# Schematic.net
KiCad netlist of a schematic drawn in EAGLE
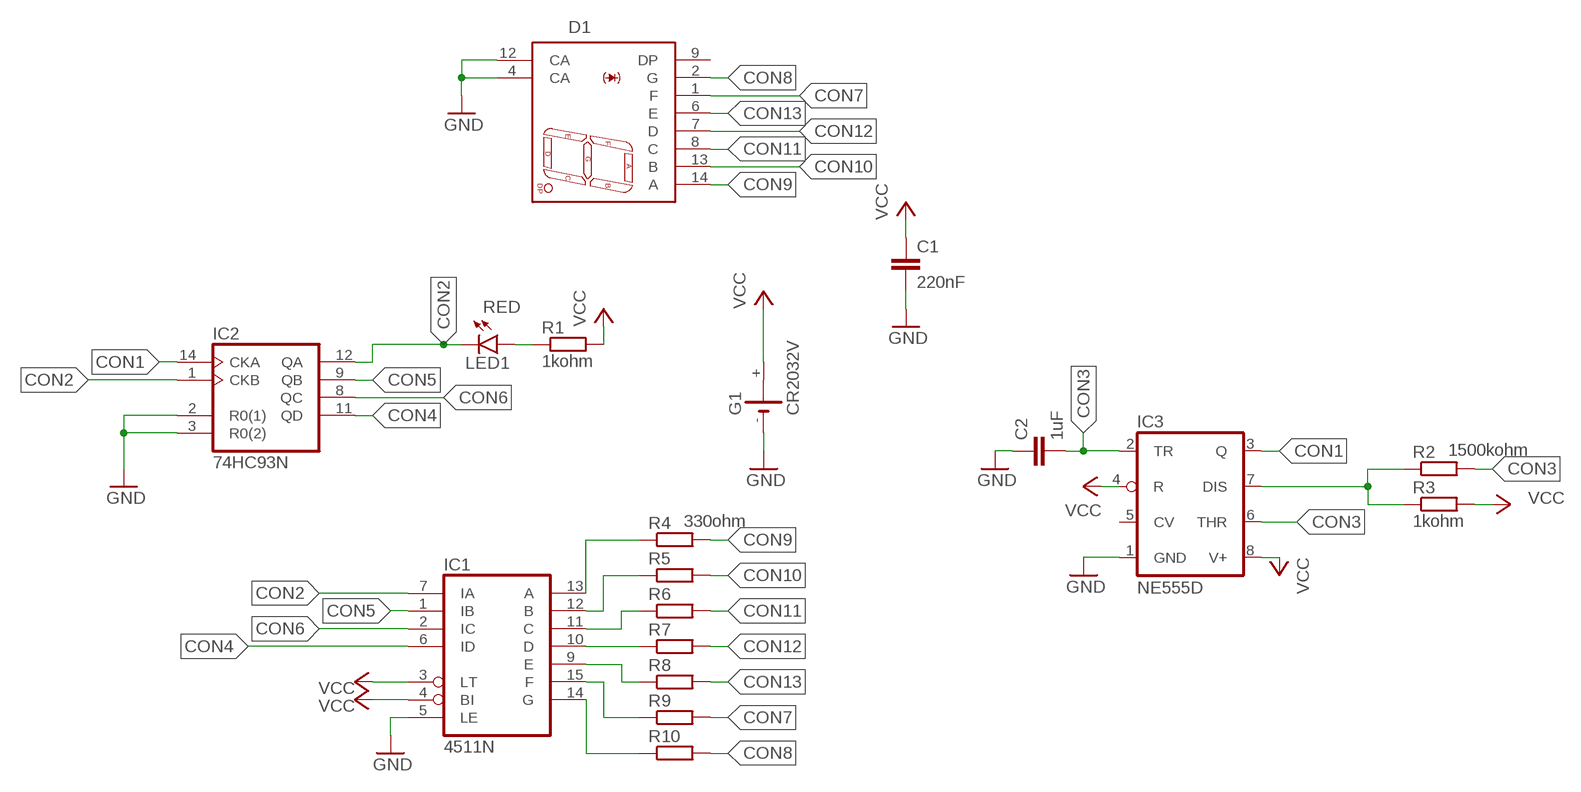
[diagram p0: schematic, sheet 1]

(export (version "E")
  (design (tool "Eeschema 10.0.6"))
  (components
    (comp (ref "C1")
      (value "220nF")
      (footprint "eagle-import:C025-025X050")
      (libsource (lib "eagle-import") (part "C-EU025-025X050"))
    )
    (comp (ref "C2")
      (value "1uF")
      (footprint "eagle-import:C025-025X050")
      (libsource (lib "eagle-import") (part "C-EU025-025X050"))
    )
    (comp (ref "D1")
      (value "SA03")
      (footprint "eagle-import:S_03")
      (libsource (lib "eagle-import") (part "SA03"))
    )
    (comp (ref "G1")
      (value "CR2032V")
      (footprint "eagle-import:CR2032V")
      (libsource (lib "eagle-import") (part "CR2032V"))
    )
    (comp (ref "IC1")
      (value "4511N")
      (footprint "eagle-import:DIL16")
      (libsource (lib "eagle-import") (part "4511N"))
    )
    (comp (ref "IC2")
      (value "74HC93N")
      (footprint "eagle-import:DIL14")
      (libsource (lib "eagle-import") (part "7493NHC"))
    )
    (comp (ref "IC3")
      (value "NE555D")
      (footprint "eagle-import:SO08")
      (libsource (lib "eagle-import") (part "555DNE"))
    )
    (comp (ref "LED1")
      (value "RED")
      (footprint "eagle-import:LED3MM")
      (libsource (lib "eagle-import") (part "LED3MM"))
    )
    (comp (ref "R1")
      (value "1kohm")
      (footprint "eagle-import:0204_7")
      (libsource (lib "eagle-import") (part "R-EU_0204/7"))
    )
    (comp (ref "R2")
      (value "1500kohm")
      (footprint "eagle-import:0204_7")
      (libsource (lib "eagle-import") (part "R-EU_0204/7"))
    )
    (comp (ref "R3")
      (value "1kohm")
      (footprint "eagle-import:0204_7")
      (libsource (lib "eagle-import") (part "R-EU_0204/7"))
    )
    (comp (ref "R4")
      (value "330ohm")
      (footprint "eagle-import:0204_7")
      (libsource (lib "eagle-import") (part "R-EU_0204/7"))
    )
    (comp (ref "R5")
      (value "R-EU_0204/7")
      (footprint "eagle-import:0204_7")
      (libsource (lib "eagle-import") (part "R-EU_0204/7"))
    )
    (comp (ref "R6")
      (value "R-EU_0204/7")
      (footprint "eagle-import:0204_7")
      (libsource (lib "eagle-import") (part "R-EU_0204/7"))
    )
    (comp (ref "R7")
      (value "R-EU_0204/7")
      (footprint "eagle-import:0204_7")
      (libsource (lib "eagle-import") (part "R-EU_0204/7"))
    )
    (comp (ref "R8")
      (value "R-EU_0204/7")
      (footprint "eagle-import:0204_7")
      (libsource (lib "eagle-import") (part "R-EU_0204/7"))
    )
    (comp (ref "R9")
      (value "R-EU_0204/7")
      (footprint "eagle-import:0204_7")
      (libsource (lib "eagle-import") (part "R-EU_0204/7"))
    )
    (comp (ref "R10")
      (value "R-EU_0204/7")
      (footprint "eagle-import:0204_7")
      (libsource (lib "eagle-import") (part "R-EU_0204/7"))
    )
  )
  (nets
    (net (code "1") (name "CON1") (class "Default")
      (node (ref "IC2") (pin "14") (pinfunction "CKA_14") (pintype "input"))
      (node (ref "IC3") (pin "3") (pinfunction "Q_3") (pintype "output"))
    )
    (net (code "2") (name "CON2") (class "Default")
      (node (ref "IC1") (pin "7") (pinfunction "IA_7") (pintype "input"))
      (node (ref "IC2") (pin "1") (pinfunction "CKB_1") (pintype "input"))
      (node (ref "IC2") (pin "12") (pinfunction "QA_12") (pintype "output"))
      (node (ref "LED1") (pin "K") (pinfunction "C_K") (pintype "passive"))
    )
    (net (code "3") (name "CON3") (class "Default")
      (node (ref "C2") (pin "2") (pinfunction "2_2") (pintype "passive"))
      (node (ref "IC3") (pin "2") (pinfunction "TR_2") (pintype "input"))
      (node (ref "IC3") (pin "6") (pinfunction "THR_6") (pintype "input"))
      (node (ref "R2") (pin "2") (pinfunction "2_2") (pintype "passive"))
    )
    (net (code "4") (name "CON4") (class "Default")
      (node (ref "IC1") (pin "6") (pinfunction "ID_6") (pintype "input"))
      (node (ref "IC2") (pin "11") (pinfunction "QD_11") (pintype "output"))
    )
    (net (code "5") (name "CON5") (class "Default")
      (node (ref "IC1") (pin "1") (pinfunction "IB_1") (pintype "input"))
      (node (ref "IC2") (pin "9") (pinfunction "QB_9") (pintype "output"))
    )
    (net (code "6") (name "CON6") (class "Default")
      (node (ref "IC1") (pin "2") (pinfunction "IC_2") (pintype "input"))
      (node (ref "IC2") (pin "8") (pinfunction "QC_8") (pintype "output"))
    )
    (net (code "7") (name "CON7") (class "Default")
      (node (ref "D1") (pin "1") (pinfunction "F_1") (pintype "passive"))
      (node (ref "R9") (pin "2") (pinfunction "2_2") (pintype "passive"))
    )
    (net (code "8") (name "CON8") (class "Default")
      (node (ref "D1") (pin "2") (pinfunction "G_2") (pintype "passive"))
      (node (ref "R10") (pin "2") (pinfunction "2_2") (pintype "passive"))
    )
    (net (code "9") (name "CON9") (class "Default")
      (node (ref "D1") (pin "14") (pinfunction "A_14") (pintype "passive"))
      (node (ref "R4") (pin "2") (pinfunction "2_2") (pintype "passive"))
    )
    (net (code "10") (name "CON10") (class "Default")
      (node (ref "D1") (pin "13") (pinfunction "B_13") (pintype "passive"))
      (node (ref "R5") (pin "2") (pinfunction "2_2") (pintype "passive"))
    )
    (net (code "11") (name "CON11") (class "Default")
      (node (ref "D1") (pin "8") (pinfunction "C_8") (pintype "passive"))
      (node (ref "R6") (pin "2") (pinfunction "2_2") (pintype "passive"))
    )
    (net (code "12") (name "CON12") (class "Default")
      (node (ref "D1") (pin "7") (pinfunction "D_7") (pintype "passive"))
      (node (ref "R7") (pin "2") (pinfunction "2_2") (pintype "passive"))
    )
    (net (code "13") (name "CON13") (class "Default")
      (node (ref "D1") (pin "6") (pinfunction "E_6") (pintype "passive"))
      (node (ref "R8") (pin "2") (pinfunction "2_2") (pintype "passive"))
    )
    (net (code "14") (name "GND") (class "Default")
      (node (ref "C1") (pin "2") (pinfunction "2_2") (pintype "passive"))
      (node (ref "C2") (pin "1") (pinfunction "1_1") (pintype "passive"))
      (node (ref "D1") (pin "12") (pinfunction "CA_12") (pintype "passive"))
      (node (ref "D1") (pin "4") (pinfunction "CA_4") (pintype "passive"))
      (node (ref "G1") (pin "-") (pinfunction "-_-") (pintype "passive"))
      (node (ref "IC1") (pin "5") (pinfunction "LE_5") (pintype "input"))
      (node (ref "IC2") (pin "2") (pinfunction "R0(1)_2") (pintype "input"))
      (node (ref "IC2") (pin "3") (pinfunction "R0(2)_3") (pintype "input"))
      (node (ref "IC3") (pin "1") (pinfunction "GND_1") (pintype "power_in"))
    )
    (net (code "15") (name "Net-(IC1A-A)") (class "Default")
      (node (ref "IC1") (pin "13") (pinfunction "A_13") (pintype "output"))
      (node (ref "R4") (pin "1") (pinfunction "1_1") (pintype "passive"))
    )
    (net (code "16") (name "Net-(IC1A-B)") (class "Default")
      (node (ref "IC1") (pin "12") (pinfunction "B_12") (pintype "output"))
      (node (ref "R5") (pin "1") (pinfunction "1_1") (pintype "passive"))
    )
    (net (code "17") (name "Net-(IC1A-C)") (class "Default")
      (node (ref "IC1") (pin "11") (pinfunction "C_11") (pintype "output"))
      (node (ref "R6") (pin "1") (pinfunction "1_1") (pintype "passive"))
    )
    (net (code "18") (name "Net-(IC1A-D)") (class "Default")
      (node (ref "IC1") (pin "10") (pinfunction "D_10") (pintype "output"))
      (node (ref "R7") (pin "1") (pinfunction "1_1") (pintype "passive"))
    )
    (net (code "19") (name "Net-(IC1A-E)") (class "Default")
      (node (ref "IC1") (pin "9") (pinfunction "E_9") (pintype "output"))
      (node (ref "R8") (pin "1") (pinfunction "1_1") (pintype "passive"))
    )
    (net (code "20") (name "Net-(IC1A-F)") (class "Default")
      (node (ref "IC1") (pin "15") (pinfunction "F_15") (pintype "output"))
      (node (ref "R9") (pin "1") (pinfunction "1_1") (pintype "passive"))
    )
    (net (code "21") (name "Net-(IC1A-G)") (class "Default")
      (node (ref "IC1") (pin "14") (pinfunction "G_14") (pintype "output"))
      (node (ref "R10") (pin "1") (pinfunction "1_1") (pintype "passive"))
    )
    (net (code "22") (name "Net-(IC3-DIS)") (class "Default")
      (node (ref "IC3") (pin "7") (pinfunction "DIS_7") (pintype "input"))
      (node (ref "R2") (pin "1") (pinfunction "1_1") (pintype "passive"))
      (node (ref "R3") (pin "1") (pinfunction "1_1") (pintype "passive"))
    )
    (net (code "23") (name "Net-(LED1-PadA)") (class "Default")
      (node (ref "LED1") (pin "A") (pinfunction "A_A") (pintype "passive"))
      (node (ref "R1") (pin "1") (pinfunction "1_1") (pintype "passive"))
    )
    (net (code "24") (name "VCC") (class "Default")
      (node (ref "C1") (pin "1") (pinfunction "1_1") (pintype "passive"))
      (node (ref "G1") (pin "+") (pinfunction "+_+") (pintype "passive"))
      (node (ref "IC1") (pin "3") (pinfunction "LT_3") (pintype "input"))
      (node (ref "IC1") (pin "4") (pinfunction "BI_4") (pintype "input"))
      (node (ref "IC3") (pin "4") (pinfunction "R_4") (pintype "input"))
      (node (ref "IC3") (pin "8") (pinfunction "V+_8") (pintype "power_in"))
      (node (ref "R1") (pin "2") (pinfunction "2_2") (pintype "passive"))
      (node (ref "R3") (pin "2") (pinfunction "2_2") (pintype "passive"))
    )
    (net (code "25") (name "unconnected-(D1-DP-Pad9)") (class "Default")
      (node (ref "D1") (pin "9") (pinfunction "DP_9") (pintype "passive"))
    )
    (net (code "26") (name "unconnected-(G1-+-Pad+@1)") (class "Default")
      (node (ref "G1") (pin "+@1") (pinfunction "+_+@1") (pintype "passive"))
    )
    (net (code "27") (name "unconnected-(IC3-CV-Pad5)") (class "Default")
      (node (ref "IC3") (pin "5") (pinfunction "CV_5") (pintype "input"))
    )
  )
)
